# powerstage.net
KiCad netlist of a schematic drawn in EAGLE
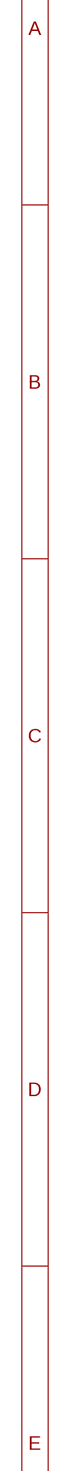
[diagram p0: schematic, sheet 1, part 1 of 2]
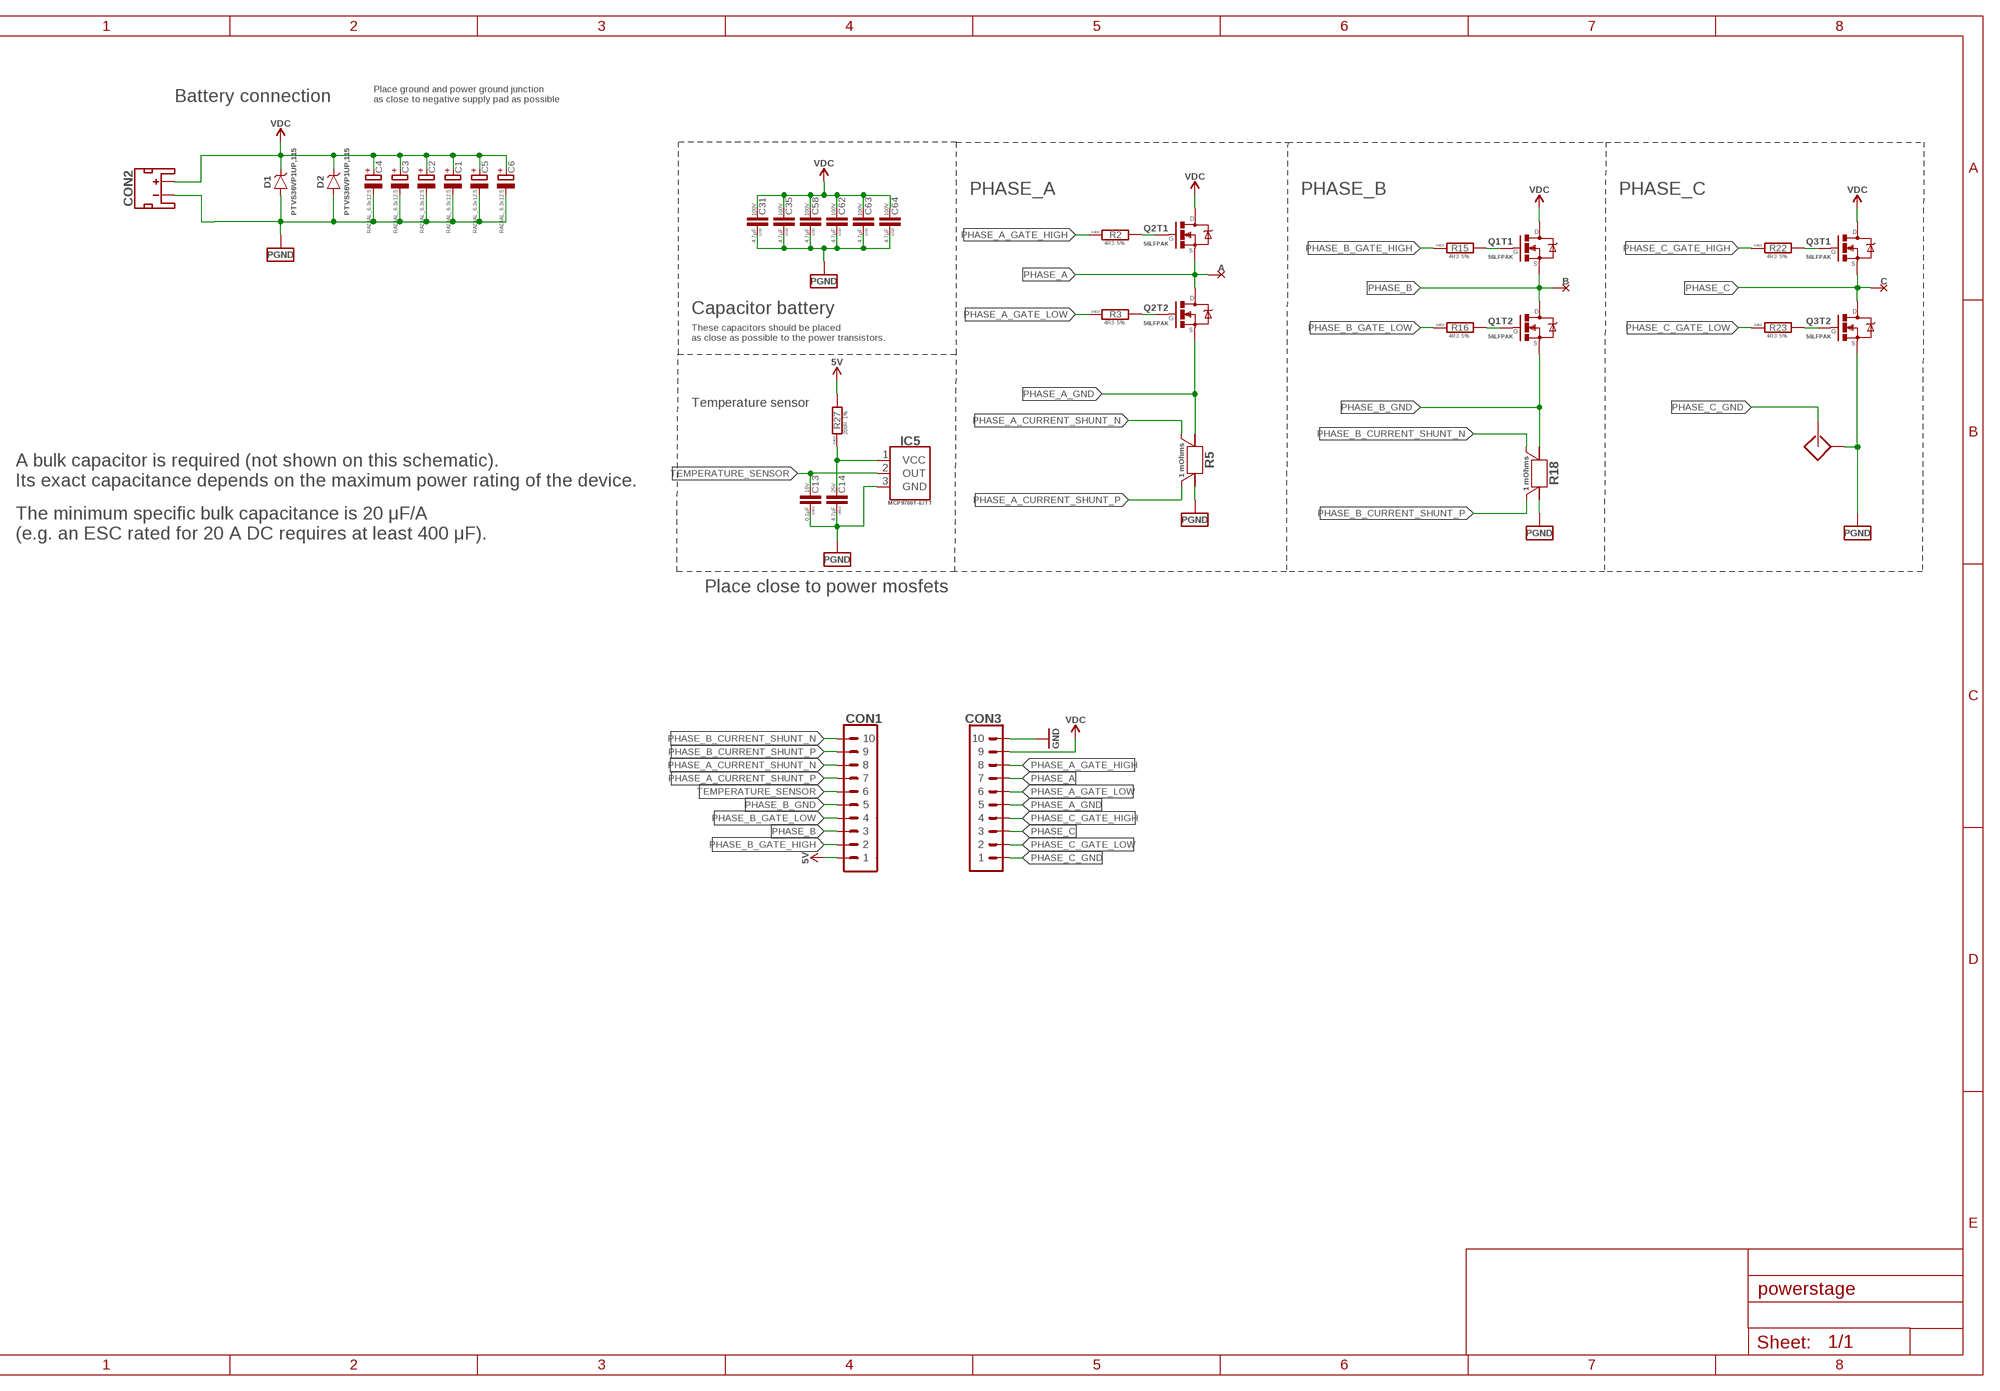
[diagram p1: schematic, sheet 1, part 2 of 2]

(export (version "E")
  (design (tool "Eeschema 10.0.6"))
  (components
    (comp (ref "A")
      (value "PAD-HOLE_2")
      (footprint "eagle-import:HOLE_2")
      (libsource (lib "eagle-import") (part "PAD-HOLE_2"))
    )
    (comp (ref "B")
      (value "PAD-HOLE_2")
      (footprint "eagle-import:HOLE_2")
      (libsource (lib "eagle-import") (part "PAD-HOLE_2"))
    )
    (comp (ref "C")
      (value "PAD-HOLE_2")
      (footprint "eagle-import:HOLE_2")
      (libsource (lib "eagle-import") (part "PAD-HOLE_2"))
    )
    (comp (ref "C1")
      (value "CPOLRADIAL-6.3X12.5-RA")
      (footprint "eagle-import:RADIAL_6.3X12.5-RA")
      (fields (field (name "PACKAGE") "RADIAL_6.3x12.5"))
      (libsource (lib "eagle-import") (part "CPOLRADIAL-6.3X12.5-RA"))
    )
    (comp (ref "C2")
      (value "CPOLRADIAL-6.3X12.5-RA")
      (footprint "eagle-import:RADIAL_6.3X12.5-RA")
      (fields (field (name "PACKAGE") "RADIAL_6.3x12.5"))
      (libsource (lib "eagle-import") (part "CPOLRADIAL-6.3X12.5-RA"))
    )
    (comp (ref "C3")
      (value "CPOLRADIAL-6.3X12.5-RA")
      (footprint "eagle-import:RADIAL_6.3X12.5-RA")
      (fields (field (name "PACKAGE") "RADIAL_6.3x12.5"))
      (libsource (lib "eagle-import") (part "CPOLRADIAL-6.3X12.5-RA"))
    )
    (comp (ref "C4")
      (value "CPOLRADIAL-6.3X12.5-RA")
      (footprint "eagle-import:RADIAL_6.3X12.5-RA")
      (fields (field (name "PACKAGE") "RADIAL_6.3x12.5"))
      (libsource (lib "eagle-import") (part "CPOLRADIAL-6.3X12.5-RA"))
    )
    (comp (ref "C5")
      (value "CPOL-RADIAL_6.3X12.5")
      (footprint "eagle-import:RADIAL_6.3X12.5")
      (fields (field (name "PACKAGE") "RADIAL_6.3x12.5"))
      (libsource (lib "eagle-import") (part "CPOL-RADIAL_6.3X12.5"))
    )
    (comp (ref "C6")
      (value "CPOL-RADIAL_6.3X12.5")
      (footprint "eagle-import:RADIAL_6.3X12.5")
      (fields (field (name "PACKAGE") "RADIAL_6.3x12.5"))
      (libsource (lib "eagle-import") (part "CPOL-RADIAL_6.3X12.5"))
    )
    (comp (ref "C13")
      (value "0.1µF")
      (footprint "eagle-import:C0402")
      (fields
        (field (name "MANF") "Murata Electronics North America")
        (field (name "PACKAGE") "0402")
        (field (name "TOLERANCE") "+-10%")
        (field (name "VOLTAGE") "16V")
      )
      (libsource (lib "eagle-import") (part "0.1µF-0402-16V_10%_X7R"))
    )
    (comp (ref "C14")
      (value "4.7µF")
      (footprint "eagle-import:C0603")
      (fields
        (field (name "MANF") "Murata Electronics North America")
        (field (name "PACKAGE") "0603")
        (field (name "TOLERANCE") "+-10%")
        (field (name "VOLTAGE") "25V")
      )
      (libsource (lib "eagle-import") (part "4.7µF-0603-25V_10%_X6S"))
    )
    (comp (ref "C31")
      (value "4.7µF")
      (footprint "eagle-import:C1210")
      (fields
        (field (name "MANF") "TDK Corporation")
        (field (name "PACKAGE") "1210")
        (field (name "TOLERANCE") "+-20%")
        (field (name "VOLTAGE") "100V")
      )
      (libsource (lib "eagle-import") (part "myxa_masterlib_1040030_4.7µF-1210-100V_20%_X7S"))
    )
    (comp (ref "C35")
      (value "4.7µF")
      (footprint "eagle-import:C1210")
      (fields
        (field (name "MANF") "TDK Corporation")
        (field (name "PACKAGE") "1210")
        (field (name "TOLERANCE") "+-20%")
        (field (name "VOLTAGE") "100V")
      )
      (libsource (lib "eagle-import") (part "myxa_masterlib_1040030_4.7µF-1210-100V_20%_X7S"))
    )
    (comp (ref "C58")
      (value "4.7µF")
      (footprint "eagle-import:C1210")
      (fields
        (field (name "MANF") "TDK Corporation")
        (field (name "PACKAGE") "1210")
        (field (name "TOLERANCE") "+-20%")
        (field (name "VOLTAGE") "100V")
      )
      (libsource (lib "eagle-import") (part "myxa_masterlib_1040030_4.7µF-1210-100V_20%_X7S"))
    )
    (comp (ref "C62")
      (value "4.7µF")
      (footprint "eagle-import:C1210")
      (fields
        (field (name "MANF") "TDK Corporation")
        (field (name "PACKAGE") "1210")
        (field (name "TOLERANCE") "+-20%")
        (field (name "VOLTAGE") "100V")
      )
      (libsource (lib "eagle-import") (part "myxa_masterlib_1040030_4.7µF-1210-100V_20%_X7S"))
    )
    (comp (ref "C63")
      (value "4.7µF")
      (footprint "eagle-import:C1210")
      (fields
        (field (name "MANF") "TDK Corporation")
        (field (name "PACKAGE") "1210")
        (field (name "TOLERANCE") "+-20%")
        (field (name "VOLTAGE") "100V")
      )
      (libsource (lib "eagle-import") (part "myxa_masterlib_1040030_4.7µF-1210-100V_20%_X7S"))
    )
    (comp (ref "C64")
      (value "4.7µF")
      (footprint "eagle-import:C1210")
      (fields
        (field (name "MANF") "TDK Corporation")
        (field (name "PACKAGE") "1210")
        (field (name "TOLERANCE") "+-20%")
        (field (name "VOLTAGE") "100V")
      )
      (libsource (lib "eagle-import") (part "myxa_masterlib_1040030_4.7µF-1210-100V_20%_X7S"))
    )
    (comp (ref "CON1")
      (value "PINHEAD_1X10-2-FEMALE")
      (footprint "eagle-import:1X10-PTH_2-FEMALE")
      (libsource (lib "eagle-import") (part "PINHEAD_1X10-2-FEMALE"))
    )
    (comp (ref "CON2")
      (value "BATTERY_CON-2P-XT30-RA")
      (footprint "eagle-import:XT30-RA")
      (fields (field (name "MANF") "AMASS"))
      (libsource (lib "eagle-import") (part "BATTERY_CON-2P-XT30-RA"))
    )
    (comp (ref "CON3")
      (value "PINHEAD_1X10-2-FEMALE")
      (footprint "eagle-import:1X10-PTH_2-FEMALE")
      (libsource (lib "eagle-import") (part "PINHEAD_1X10-2-FEMALE"))
    )
    (comp (ref "D1")
      (value "PTVS36VP1UP,115-36V-SOD128")
      (footprint "eagle-import:SOD128")
      (fields (field (name "MANF") "Nexperia USA Inc") (field (name "MANF#") "PTVS36VP1UP,115"))
      (libsource (lib "eagle-import") (part "PTVS36VP1UP,115-SOD128-36V"))
    )
    (comp (ref "D2")
      (value "PTVS36VP1UP,115-36V-SOD128")
      (footprint "eagle-import:SOD128")
      (fields (field (name "MANF") "Nexperia USA Inc") (field (name "MANF#") "PTVS36VP1UP,115"))
      (libsource (lib "eagle-import") (part "PTVS36VP1UP,115-SOD128-36V"))
    )
    (comp (ref "IC5")
      (value "MCP9700")
      (footprint "eagle-import:SOT23B-3")
      (fields (field (name "MANF#") "MCP9700T-E/TT") (field (name "MANF") "Microchip Technology"))
      (libsource (lib "eagle-import") (part "MCP9700"))
    )
    (comp (ref "Q1")
      (value "BUK7K6R2-40EX")
      (footprint "eagle-import:SOT-1205")
      (fields (field (name "PACKAGE") "56LFPAK") (field (name "MANF") "NXP Semiconductors"))
      (libsource (lib "eagle-import") (part "BUK7K6R2-40EX"))
    )
    (comp (ref "Q2")
      (value "BUK7K6R2-40EX")
      (footprint "eagle-import:SOT-1205")
      (fields (field (name "PACKAGE") "56LFPAK") (field (name "MANF") "NXP Semiconductors"))
      (libsource (lib "eagle-import") (part "BUK7K6R2-40EX"))
    )
    (comp (ref "Q3")
      (value "BUK7K6R2-40EX")
      (footprint "eagle-import:SOT-1205")
      (fields (field (name "PACKAGE") "56LFPAK") (field (name "MANF") "NXP Semiconductors"))
      (libsource (lib "eagle-import") (part "BUK7K6R2-40EX"))
    )
    (comp (ref "R2")
      (value "4R3")
      (footprint "eagle-import:R0402")
      (fields (field (name "MANF") "Yageo") (field (name "PACKAGE") "0402") (field (name "TOLERANCE") "5%"))
      (libsource (lib "eagle-import") (part "4R3-0402-5%"))
    )
    (comp (ref "R3")
      (value "4R3")
      (footprint "eagle-import:R0402")
      (fields (field (name "MANF") "Yageo") (field (name "PACKAGE") "0402") (field (name "TOLERANCE") "5%"))
      (libsource (lib "eagle-import") (part "4R3-0402-5%"))
    )
    (comp (ref "R5")
      (value "1 mOhms")
      (footprint "eagle-import:R2512-KELVIN")
      (fields
        (field (name "MANF") "Stackpole Electronics Inc.")
        (field (name "POWER") "2W")
        (field (name "TOLERANCE") "±1%")
      )
      (libsource (lib "eagle-import") (part "CURRENT_SHUNT_KELVIN-2512-KELVIN-0.001R"))
    )
    (comp (ref "R15")
      (value "4R3")
      (footprint "eagle-import:R0402")
      (fields (field (name "MANF") "Yageo") (field (name "PACKAGE") "0402") (field (name "TOLERANCE") "5%"))
      (libsource (lib "eagle-import") (part "4R3-0402-5%"))
    )
    (comp (ref "R16")
      (value "4R3")
      (footprint "eagle-import:R0402")
      (fields (field (name "MANF") "Yageo") (field (name "PACKAGE") "0402") (field (name "TOLERANCE") "5%"))
      (libsource (lib "eagle-import") (part "4R3-0402-5%"))
    )
    (comp (ref "R18")
      (value "1 mOhms")
      (footprint "eagle-import:R2512-KELVIN")
      (fields
        (field (name "MANF") "Stackpole Electronics Inc.")
        (field (name "POWER") "2W")
        (field (name "TOLERANCE") "±1%")
      )
      (libsource (lib "eagle-import") (part "CURRENT_SHUNT_KELVIN-2512-KELVIN-0.001R"))
    )
    (comp (ref "R22")
      (value "4R3")
      (footprint "eagle-import:R0402")
      (fields (field (name "MANF") "Yageo") (field (name "PACKAGE") "0402") (field (name "TOLERANCE") "5%"))
      (libsource (lib "eagle-import") (part "4R3-0402-5%"))
    )
    (comp (ref "R23")
      (value "4R3")
      (footprint "eagle-import:R0402")
      (fields (field (name "MANF") "Yageo") (field (name "PACKAGE") "0402") (field (name "TOLERANCE") "5%"))
      (libsource (lib "eagle-import") (part "4R3-0402-5%"))
    )
    (comp (ref "R27")
      (value "200R")
      (footprint "eagle-import:R0402")
      (fields (field (name "MANF") "Yageo") (field (name "PACKAGE") "0402") (field (name "TOLERANCE") "1%"))
      (libsource (lib "eagle-import") (part "200R-0402-1%"))
    )
    (comp (ref "S1")
      (value "SENSE")
      (footprint "eagle-import:SENSE-0.6")
      (libsource (lib "eagle-import") (part "SENSE"))
    )
  )
  (nets
    (net (code "1") (name "5V") (class "Default")
      (node (ref "CON1") (pin "1") (pinfunction "1_1") (pintype "passive"))
      (node (ref "R27") (pin "2") (pinfunction "2_2") (pintype "passive"))
    )
    (net (code "2") (name "GND") (class "Default")
      (node (ref "CON3") (pin "10") (pinfunction "10_10") (pintype "passive"))
    )
    (net (code "3") (name "Net-(C14-2)") (class "Default")
      (node (ref "C14") (pin "P$2") (pinfunction "2_P$2") (pintype "passive"))
      (node (ref "IC5") (pin "1") (pinfunction "VCC_1") (pintype "bidirectional"))
      (node (ref "R27") (pin "1") (pinfunction "1_1") (pintype "passive"))
    )
    (net (code "4") (name "Net-(Q1A-G)") (class "Default")
      (node (ref "Q1") (pin "2") (pinfunction "G_2") (pintype "passive"))
      (node (ref "R15") (pin "2") (pinfunction "2_2") (pintype "passive"))
    )
    (net (code "5") (name "Net-(Q1B-G)") (class "Default")
      (node (ref "Q1") (pin "4") (pinfunction "G_4") (pintype "passive"))
      (node (ref "R16") (pin "2") (pinfunction "2_2") (pintype "passive"))
    )
    (net (code "6") (name "Net-(Q2A-G)") (class "Default")
      (node (ref "Q2") (pin "2") (pinfunction "G_2") (pintype "passive"))
      (node (ref "R2") (pin "2") (pinfunction "2_2") (pintype "passive"))
    )
    (net (code "7") (name "Net-(Q2B-G)") (class "Default")
      (node (ref "Q2") (pin "4") (pinfunction "G_4") (pintype "passive"))
      (node (ref "R3") (pin "2") (pinfunction "2_2") (pintype "passive"))
    )
    (net (code "8") (name "Net-(Q3A-G)") (class "Default")
      (node (ref "Q3") (pin "2") (pinfunction "G_2") (pintype "passive"))
      (node (ref "R22") (pin "2") (pinfunction "2_2") (pintype "passive"))
    )
    (net (code "9") (name "Net-(Q3B-G)") (class "Default")
      (node (ref "Q3") (pin "4") (pinfunction "G_4") (pintype "passive"))
      (node (ref "R23") (pin "2") (pinfunction "2_2") (pintype "passive"))
    )
    (net (code "10") (name "PGND") (class "Default")
      (node (ref "C1") (pin "-") (pinfunction "-_-") (pintype "passive"))
      (node (ref "C13") (pin "1") (pinfunction "1_1") (pintype "passive"))
      (node (ref "C14") (pin "P$1") (pinfunction "1_P$1") (pintype "passive"))
      (node (ref "C2") (pin "-") (pinfunction "-_-") (pintype "passive"))
      (node (ref "C3") (pin "-") (pinfunction "-_-") (pintype "passive"))
      (node (ref "C31") (pin "1") (pinfunction "1_1") (pintype "passive"))
      (node (ref "C35") (pin "1") (pinfunction "1_1") (pintype "passive"))
      (node (ref "C4") (pin "-") (pinfunction "-_-") (pintype "passive"))
      (node (ref "C5") (pin "-") (pinfunction "-_-") (pintype "passive"))
      (node (ref "C58") (pin "1") (pinfunction "1_1") (pintype "passive"))
      (node (ref "C6") (pin "-") (pinfunction "-_-") (pintype "passive"))
      (node (ref "C62") (pin "1") (pinfunction "1_1") (pintype "passive"))
      (node (ref "C63") (pin "1") (pinfunction "1_1") (pintype "passive"))
      (node (ref "C64") (pin "1") (pinfunction "1_1") (pintype "passive"))
      (node (ref "CON2") (pin "-") (pinfunction "-_-") (pintype "bidirectional"))
      (node (ref "D1") (pin "A") (pinfunction "A_A") (pintype "passive"))
      (node (ref "D2") (pin "A") (pinfunction "A_A") (pintype "passive"))
      (node (ref "IC5") (pin "3") (pinfunction "GND_3") (pintype "bidirectional"))
      (node (ref "Q3") (pin "3") (pinfunction "S_3") (pintype "passive"))
      (node (ref "R18") (pin "2") (pinfunction "2_2") (pintype "bidirectional"))
      (node (ref "R18") (pin "22") (pinfunction "2_22") (pintype "bidirectional"))
      (node (ref "R5") (pin "2") (pinfunction "2_2") (pintype "bidirectional"))
      (node (ref "R5") (pin "22") (pinfunction "2_22") (pintype "bidirectional"))
      (node (ref "S1") (pin "SHELL") (pinfunction "SHELLL_SHELL") (pintype "bidirectional"))
    )
    (net (code "11") (name "PHASE_A") (class "Default")
      (node (ref "A") (pin "P$1") (pinfunction "P$1_P$1") (pintype "bidirectional"))
      (node (ref "CON3") (pin "7") (pinfunction "7_7") (pintype "passive"))
      (node (ref "Q2") (pin "1") (pinfunction "S_1") (pintype "passive"))
      (node (ref "Q2") (pin "5") (pinfunction "D_5") (pintype "passive"))
      (node (ref "Q2") (pin "6") (pinfunction "D_6") (pintype "passive"))
      (node (ref "Q2") (pin "EP-5-6") (pinfunction "D_EP-5-6") (pintype "passive"))
    )
    (net (code "12") (name "PHASE_A_CURRENT_SHUNT_N") (class "Default")
      (node (ref "CON1") (pin "8") (pinfunction "8_8") (pintype "passive"))
      (node (ref "R5") (pin "S1") (pinfunction "S1_S1") (pintype "bidirectional"))
    )
    (net (code "13") (name "PHASE_A_CURRENT_SHUNT_P") (class "Default")
      (node (ref "CON1") (pin "7") (pinfunction "7_7") (pintype "passive"))
      (node (ref "R5") (pin "S2") (pinfunction "S2_S2") (pintype "bidirectional"))
    )
    (net (code "14") (name "PHASE_A_GATE_HIGH") (class "Default")
      (node (ref "CON3") (pin "8") (pinfunction "8_8") (pintype "passive"))
      (node (ref "R2") (pin "1") (pinfunction "1_1") (pintype "passive"))
    )
    (net (code "15") (name "PHASE_A_GATE_LOW") (class "Default")
      (node (ref "CON3") (pin "6") (pinfunction "6_6") (pintype "passive"))
      (node (ref "R3") (pin "1") (pinfunction "1_1") (pintype "passive"))
    )
    (net (code "16") (name "PHASE_A_GND") (class "Default")
      (node (ref "CON3") (pin "5") (pinfunction "5_5") (pintype "passive"))
      (node (ref "Q2") (pin "3") (pinfunction "S_3") (pintype "passive"))
      (node (ref "R5") (pin "1") (pinfunction "1_1") (pintype "bidirectional"))
      (node (ref "R5") (pin "11") (pinfunction "1_11") (pintype "bidirectional"))
    )
    (net (code "17") (name "PHASE_B") (class "Default")
      (node (ref "B") (pin "P$1") (pinfunction "P$1_P$1") (pintype "bidirectional"))
      (node (ref "CON1") (pin "3") (pinfunction "3_3") (pintype "passive"))
      (node (ref "Q1") (pin "1") (pinfunction "S_1") (pintype "passive"))
      (node (ref "Q1") (pin "5") (pinfunction "D_5") (pintype "passive"))
      (node (ref "Q1") (pin "6") (pinfunction "D_6") (pintype "passive"))
      (node (ref "Q1") (pin "EP-5-6") (pinfunction "D_EP-5-6") (pintype "passive"))
    )
    (net (code "18") (name "PHASE_B_CURRENT_SHUNT_N") (class "Default")
      (node (ref "CON1") (pin "10") (pinfunction "10_10") (pintype "passive"))
      (node (ref "R18") (pin "S1") (pinfunction "S1_S1") (pintype "bidirectional"))
    )
    (net (code "19") (name "PHASE_B_CURRENT_SHUNT_P") (class "Default")
      (node (ref "CON1") (pin "9") (pinfunction "9_9") (pintype "passive"))
      (node (ref "R18") (pin "S2") (pinfunction "S2_S2") (pintype "bidirectional"))
    )
    (net (code "20") (name "PHASE_B_GATE_HIGH") (class "Default")
      (node (ref "CON1") (pin "2") (pinfunction "2_2") (pintype "passive"))
      (node (ref "R15") (pin "1") (pinfunction "1_1") (pintype "passive"))
    )
    (net (code "21") (name "PHASE_B_GATE_LOW") (class "Default")
      (node (ref "CON1") (pin "4") (pinfunction "4_4") (pintype "passive"))
      (node (ref "R16") (pin "1") (pinfunction "1_1") (pintype "passive"))
    )
    (net (code "22") (name "PHASE_B_GND") (class "Default")
      (node (ref "CON1") (pin "5") (pinfunction "5_5") (pintype "passive"))
      (node (ref "Q1") (pin "3") (pinfunction "S_3") (pintype "passive"))
      (node (ref "R18") (pin "1") (pinfunction "1_1") (pintype "bidirectional"))
      (node (ref "R18") (pin "11") (pinfunction "1_11") (pintype "bidirectional"))
    )
    (net (code "23") (name "PHASE_C") (class "Default")
      (node (ref "C") (pin "P$1") (pinfunction "P$1_P$1") (pintype "bidirectional"))
      (node (ref "CON3") (pin "3") (pinfunction "3_3") (pintype "passive"))
      (node (ref "Q3") (pin "1") (pinfunction "S_1") (pintype "passive"))
      (node (ref "Q3") (pin "5") (pinfunction "D_5") (pintype "passive"))
      (node (ref "Q3") (pin "6") (pinfunction "D_6") (pintype "passive"))
      (node (ref "Q3") (pin "EP-5-6") (pinfunction "D_EP-5-6") (pintype "passive"))
    )
    (net (code "24") (name "PHASE_C_GATE_HIGH") (class "Default")
      (node (ref "CON3") (pin "4") (pinfunction "4_4") (pintype "passive"))
      (node (ref "R22") (pin "1") (pinfunction "1_1") (pintype "passive"))
    )
    (net (code "25") (name "PHASE_C_GATE_LOW") (class "Default")
      (node (ref "CON3") (pin "2") (pinfunction "2_2") (pintype "passive"))
      (node (ref "R23") (pin "1") (pinfunction "1_1") (pintype "passive"))
    )
    (net (code "26") (name "PHASE_C_GND") (class "Default")
      (node (ref "CON3") (pin "1") (pinfunction "1_1") (pintype "passive"))
      (node (ref "S1") (pin "IN") (pinfunction "IN_IN") (pintype "bidirectional"))
    )
    (net (code "27") (name "TEMPERATURE_SENSOR") (class "Default")
      (node (ref "C13") (pin "2") (pinfunction "2_2") (pintype "passive"))
      (node (ref "CON1") (pin "6") (pinfunction "6_6") (pintype "passive"))
      (node (ref "IC5") (pin "2") (pinfunction "OUT_2") (pintype "bidirectional"))
    )
    (net (code "28") (name "VDC") (class "Default")
      (node (ref "C1") (pin "+") (pinfunction "+_+") (pintype "passive"))
      (node (ref "C2") (pin "+") (pinfunction "+_+") (pintype "passive"))
      (node (ref "C3") (pin "+") (pinfunction "+_+") (pintype "passive"))
      (node (ref "C31") (pin "2") (pinfunction "2_2") (pintype "passive"))
      (node (ref "C35") (pin "2") (pinfunction "2_2") (pintype "passive"))
      (node (ref "C4") (pin "+") (pinfunction "+_+") (pintype "passive"))
      (node (ref "C5") (pin "+") (pinfunction "+_+") (pintype "passive"))
      (node (ref "C58") (pin "2") (pinfunction "2_2") (pintype "passive"))
      (node (ref "C6") (pin "+") (pinfunction "+_+") (pintype "passive"))
      (node (ref "C62") (pin "2") (pinfunction "2_2") (pintype "passive"))
      (node (ref "C63") (pin "2") (pinfunction "2_2") (pintype "passive"))
      (node (ref "C64") (pin "2") (pinfunction "2_2") (pintype "passive"))
      (node (ref "CON2") (pin "+") (pinfunction "+_+") (pintype "bidirectional"))
      (node (ref "CON3") (pin "9") (pinfunction "9_9") (pintype "passive"))
      (node (ref "D1") (pin "C") (pinfunction "C_C") (pintype "passive"))
      (node (ref "D2") (pin "C") (pinfunction "C_C") (pintype "passive"))
      (node (ref "Q1") (pin "7") (pinfunction "D_7") (pintype "passive"))
      (node (ref "Q1") (pin "8") (pinfunction "D_8") (pintype "passive"))
      (node (ref "Q1") (pin "EP-7-8") (pinfunction "D_EP-7-8") (pintype "passive"))
      (node (ref "Q2") (pin "7") (pinfunction "D_7") (pintype "passive"))
      (node (ref "Q2") (pin "8") (pinfunction "D_8") (pintype "passive"))
      (node (ref "Q2") (pin "EP-7-8") (pinfunction "D_EP-7-8") (pintype "passive"))
      (node (ref "Q3") (pin "7") (pinfunction "D_7") (pintype "passive"))
      (node (ref "Q3") (pin "8") (pinfunction "D_8") (pintype "passive"))
      (node (ref "Q3") (pin "EP-7-8") (pinfunction "D_EP-7-8") (pintype "passive"))
    )
    (net (code "29") (name "unconnected-(CON2-PAD1-PadP$3)") (class "Default")
      (node (ref "CON2") (pin "P$3") (pinfunction "PAD1_P$3") (pintype "bidirectional"))
    )
    (net (code "30") (name "unconnected-(CON2-PAD2-PadP$4)") (class "Default")
      (node (ref "CON2") (pin "P$4") (pinfunction "PAD2_P$4") (pintype "bidirectional"))
    )
  )
)
